# ESP01_Breakout.net
KiCad netlist of a schematic drawn in EAGLE
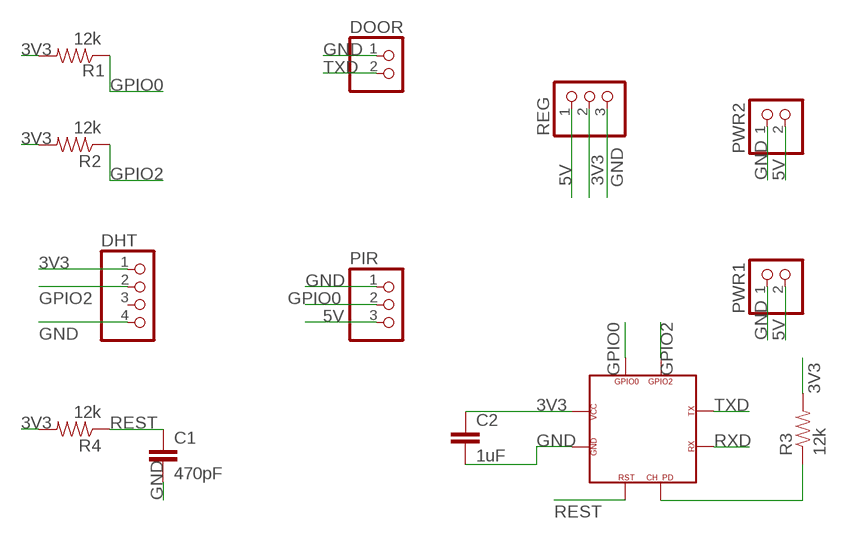
[diagram p0: schematic, sheet 1]

(export (version "E")
  (design (tool "Eeschema 10.0.6"))
  (components
    (comp (ref "C1")
      (value "470pF")
      (footprint "eagle-import:CAP-PTH-SMALLEZ")
      (libsource (lib "eagle-import") (part "CAPEZ"))
    )
    (comp (ref "C2")
      (value "1uF")
      (footprint "eagle-import:CAP-PTH-SMALLEZ")
      (libsource (lib "eagle-import") (part "CAPEZ"))
    )
    (comp (ref "DHT")
      (value "PINHD-1X4")
      (footprint "eagle-import:1X04")
      (libsource (lib "eagle-import") (part "PINHD-1X4"))
    )
    (comp (ref "DOOR")
      (value "PINHD-1X2/90")
      (footprint "eagle-import:1X02_90")
      (libsource (lib "eagle-import") (part "PINHD-1X2/90"))
    )
    (comp (ref "PIR")
      (value "PINHD-1X3")
      (footprint "eagle-import:1X03")
      (libsource (lib "eagle-import") (part "PINHD-1X3"))
    )
    (comp (ref "PWR1")
      (value "PINHD-1X2/90")
      (footprint "eagle-import:1X02_90")
      (libsource (lib "eagle-import") (part "PINHD-1X2/90"))
    )
    (comp (ref "PWR2")
      (value "PINHD-1X2/90")
      (footprint "eagle-import:1X02_90")
      (libsource (lib "eagle-import") (part "PINHD-1X2/90"))
    )
    (comp (ref "R1")
      (value "12k")
      (footprint "eagle-import:AXIAL-0.4")
      (libsource (lib "eagle-import") (part "RESISTORPTH-1/4W"))
    )
    (comp (ref "R2")
      (value "12k")
      (footprint "eagle-import:AXIAL-0.4")
      (libsource (lib "eagle-import") (part "RESISTORPTH-1/4W"))
    )
    (comp (ref "R3")
      (value "12k")
      (footprint "eagle-import:AXIAL-0.4")
      (libsource (lib "eagle-import") (part "RESISTORPTH-1/4W"))
    )
    (comp (ref "R4")
      (value "12k")
      (footprint "eagle-import:AXIAL-0.4")
      (libsource (lib "eagle-import") (part "RESISTORPTH-1/4W"))
    )
    (comp (ref "REG")
      (value "PINHD-1X3")
      (footprint "eagle-import:1X03")
      (libsource (lib "eagle-import") (part "PINHD-1X3"))
    )
    (comp (ref "U$2")
      (value "ESP-01")
      (footprint "eagle-import:ESP-01")
      (libsource (lib "eagle-import") (part "ESP-01"))
    )
  )
  (nets
    (net (code "1") (name "/3V3") (class "Default")
      (node (ref "C2") (pin "1") (pinfunction "1_1") (pintype "passive"))
      (node (ref "DHT") (pin "1") (pinfunction "1_1") (pintype "passive"))
      (node (ref "R1") (pin "P$2") (pinfunction "2_P$2") (pintype "passive"))
      (node (ref "R2") (pin "P$2") (pinfunction "2_P$2") (pintype "passive"))
      (node (ref "R3") (pin "P$2") (pinfunction "2_P$2") (pintype "passive"))
      (node (ref "R4") (pin "P$2") (pinfunction "2_P$2") (pintype "passive"))
      (node (ref "REG") (pin "2") (pinfunction "2_2") (pintype "passive"))
      (node (ref "U$2") (pin "VCC") (pinfunction "VCC_VCC") (pintype "bidirectional"))
    )
    (net (code "2") (name "/5V") (class "Default")
      (node (ref "PIR") (pin "3") (pinfunction "3_3") (pintype "passive"))
      (node (ref "PWR1") (pin "2") (pinfunction "2_2") (pintype "passive"))
      (node (ref "PWR2") (pin "2") (pinfunction "2_2") (pintype "passive"))
      (node (ref "REG") (pin "1") (pinfunction "1_1") (pintype "passive"))
    )
    (net (code "3") (name "/GND") (class "Default")
      (node (ref "C1") (pin "2") (pinfunction "2_2") (pintype "passive"))
      (node (ref "C2") (pin "2") (pinfunction "2_2") (pintype "passive"))
      (node (ref "DHT") (pin "4") (pinfunction "4_4") (pintype "passive"))
      (node (ref "DOOR") (pin "1") (pinfunction "1_1") (pintype "passive"))
      (node (ref "PIR") (pin "1") (pinfunction "1_1") (pintype "passive"))
      (node (ref "PWR1") (pin "1") (pinfunction "1_1") (pintype "passive"))
      (node (ref "PWR2") (pin "1") (pinfunction "1_1") (pintype "passive"))
      (node (ref "REG") (pin "3") (pinfunction "3_3") (pintype "passive"))
      (node (ref "U$2") (pin "GND") (pinfunction "GND_GND") (pintype "bidirectional"))
    )
    (net (code "4") (name "/GPIO0") (class "Default")
      (node (ref "PIR") (pin "2") (pinfunction "2_2") (pintype "passive"))
      (node (ref "R1") (pin "P$1") (pinfunction "1_P$1") (pintype "passive"))
      (node (ref "U$2") (pin "GPIO0") (pinfunction "GPIO0_GPIO0") (pintype "bidirectional"))
    )
    (net (code "5") (name "/GPIO2") (class "Default")
      (node (ref "DHT") (pin "2") (pinfunction "2_2") (pintype "passive"))
      (node (ref "R2") (pin "P$1") (pinfunction "1_P$1") (pintype "passive"))
      (node (ref "U$2") (pin "GPIO2") (pinfunction "GPIO2_GPIO2") (pintype "bidirectional"))
    )
    (net (code "6") (name "/REST") (class "Default")
      (node (ref "C1") (pin "1") (pinfunction "1_1") (pintype "passive"))
      (node (ref "R4") (pin "P$1") (pinfunction "1_P$1") (pintype "passive"))
      (node (ref "U$2") (pin "RST") (pinfunction "RST_RST") (pintype "bidirectional"))
    )
    (net (code "7") (name "/RXD") (class "Default")
      (node (ref "U$2") (pin "RXD") (pinfunction "RX_RXD") (pintype "bidirectional"))
    )
    (net (code "8") (name "/TXD") (class "Default")
      (node (ref "DOOR") (pin "2") (pinfunction "2_2") (pintype "passive"))
      (node (ref "U$2") (pin "TXD") (pinfunction "TX_TXD") (pintype "bidirectional"))
    )
    (net (code "9") (name "Net-(R3-1)") (class "Default")
      (node (ref "R3") (pin "P$1") (pinfunction "1_P$1") (pintype "passive"))
      (node (ref "U$2") (pin "CH_PD") (pinfunction "CP_PD_CH_PD") (pintype "bidirectional"))
    )
    (net (code "10") (name "unconnected-(DHT-Pad3)") (class "Default")
      (node (ref "DHT") (pin "3") (pinfunction "3_3") (pintype "passive"))
    )
  )
)
